# BT2.net
KiCad netlist of a schematic drawn in Altium Designer
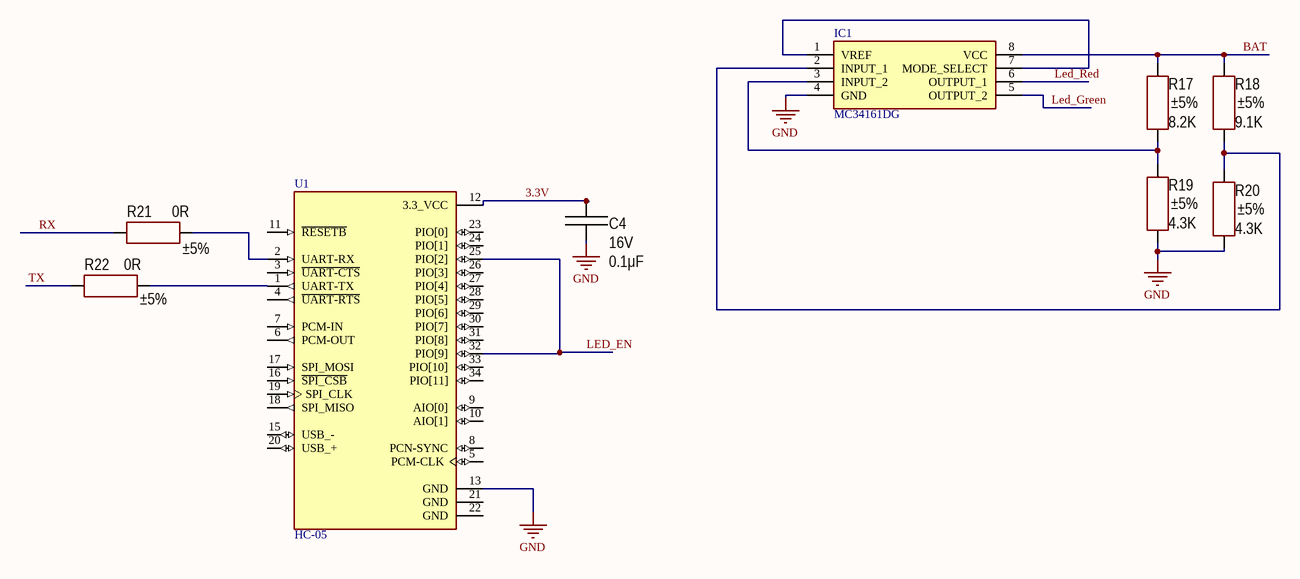
[diagram p0: BT2.SchDoc]

(export (version "E")
  (design (tool "Eeschema 10.0.6"))
  (components
    (comp (ref "C4")
      (value "0.1μF")
      (footprint "standard-case:CAP: 0805")
      (fields
        (field (name "MANUFACTURER") "Yageo")
        (field (name "PARTNUMBER") "CC0805KRX7R7BB104")
        (field (name "VALUEMANUFACTURERPARTNUMBER") "Ceramic capacitor, 0.1μF, X7R, ±10%, 16V, 0805, -55...+125°C")
        (field (name "VOLTAGE") "16V")
      )
      (libsource (lib "capacitor") (part "Ceramic_0805"))
    )
    (comp (ref "IC1")
      (value "MC34161DG")
      (footprint "SamacSys:SOIC127P600X175-8N")
      (description "Integrated Circuit")
      (fields (field (name "MOUSER PART NUMBER") "863-MC34161DG"))
      (libsource (lib "*") (part "MC34161DG"))
    )
    (comp (ref "R17")
      (value "8.2K")
      (footprint "standard-case:RES: 0805")
      (fields
        (field (name "MANUFACTURER") "Yageo")
        (field (name "PARTNUMBER") "RC0805JR-078K2L")
        (field (name "VALUEMANUFACTURERPARTNUMBER") "Resistor film, 8.2K, ±5%, 0805, 0.125W, -55...+125°C")
        (field (name "TOLERANCE") "±5%")
      )
      (libsource (lib "") (part "Resistor_0805_1"))
    )
    (comp (ref "R18")
      (value "9.1K")
      (footprint "standard-case:RES: 0805")
      (fields
        (field (name "MANUFACTURER") "Yageo")
        (field (name "PARTNUMBER") "RC0805JR-079K1L")
        (field (name "VALUEMANUFACTURERPARTNUMBER") "Resistor film, 9.1K, ±5%, 0805, 0.125W, -55...+125°C")
        (field (name "TOLERANCE") "±5%")
      )
      (libsource (lib "") (part "Resistor_0805_1"))
    )
    (comp (ref "R19")
      (value "4.3K")
      (footprint "standard-case:RES: 0805")
      (fields
        (field (name "MANUFACTURER") "Yageo")
        (field (name "PARTNUMBER") "RC0805JR-074K3L")
        (field (name "VALUEMANUFACTURERPARTNUMBER") "Resistor film, 4.3K, ±5%, 0805, 0.125W, -55...+125°C")
        (field (name "TOLERANCE") "±5%")
      )
      (libsource (lib "") (part "Resistor_0805_1"))
    )
    (comp (ref "R20")
      (value "4.3K")
      (footprint "standard-case:RES: 0805")
      (fields
        (field (name "MANUFACTURER") "Yageo")
        (field (name "PARTNUMBER") "RC0805JR-074K3L")
        (field (name "VALUEMANUFACTURERPARTNUMBER") "Resistor film, 4.3K, ±5%, 0805, 0.125W, -55...+125°C")
        (field (name "TOLERANCE") "±5%")
      )
      (libsource (lib "") (part "Resistor_0805_1"))
    )
    (comp (ref "R21")
      (value "0R")
      (footprint "standard-case:RES: 0805")
      (fields
        (field (name "MANUFACTURER") "Yageo")
        (field (name "PARTNUMBER") "RC0805JR-070RL")
        (field (name "VALUEMANUFACTURERPARTNUMBER") "Resistor film, 0R, ±5%, 0805, 0.125W, -55...+125°C")
        (field (name "TOLERANCE") "±5%")
      )
      (libsource (lib "resistor") (part "Resistor_0805"))
    )
    (comp (ref "R22")
      (value "0R")
      (footprint "standard-case:RES: 0805")
      (fields
        (field (name "MANUFACTURER") "Yageo")
        (field (name "PARTNUMBER") "RC0805JR-070RL")
        (field (name "VALUEMANUFACTURERPARTNUMBER") "Resistor film, 0R, ±5%, 0805, 0.125W, -55...+125°C")
        (field (name "TOLERANCE") "±5%")
      )
      (libsource (lib "resistor") (part "Resistor_0805"))
    )
    (comp (ref "U1")
      (value "HC-05")
      (footprint "XCVR_HC-05")
      (description "Bluetooth to Serial Port Module")
      (fields (field (name "MF") "ITead Studio"))
      (libsource (lib "HC-05 (1)") (part "HC-05"))
    )
  )
  (nets
    (net (code "1") (name "/3.3V") (class "Default")
      (node (ref "C4") (pin "2") (pinfunction "2_2") (pintype "passive"))
      (node (ref "U1") (pin "12") (pinfunction "3.3_VCC_12") (pintype "power_in"))
    )
    (net (code "2") (name "/BAT") (class "Default")
      (node (ref "IC1") (pin "8") (pinfunction "VCC_8") (pintype "passive"))
      (node (ref "R17") (pin "2") (pinfunction "2_2") (pintype "passive"))
      (node (ref "R18") (pin "2") (pinfunction "2_2") (pintype "passive"))
    )
    (net (code "3") (name "/LED_EN") (class "Default")
      (node (ref "U1") (pin "25") (pinfunction "PIO[2]_25") (pintype "bidirectional"))
      (node (ref "U1") (pin "32") (pinfunction "PIO[9]_32") (pintype "bidirectional"))
    )
    (net (code "4") (name "/Led_Green") (class "Default")
      (node (ref "IC1") (pin "5") (pinfunction "OUTPUT_2_5") (pintype "passive"))
    )
    (net (code "5") (name "/Led_Red") (class "Default")
      (node (ref "IC1") (pin "6") (pinfunction "OUTPUT_1_6") (pintype "passive"))
    )
    (net (code "6") (name "/RX") (class "Default")
      (node (ref "R21") (pin "1") (pinfunction "1_1") (pintype "passive"))
    )
    (net (code "7") (name "/TX") (class "Default")
      (node (ref "R22") (pin "1") (pinfunction "1_1") (pintype "passive"))
    )
    (net (code "8") (name "GND") (class "Default")
      (node (ref "C4") (pin "1") (pinfunction "1_1") (pintype "passive"))
      (node (ref "IC1") (pin "4") (pinfunction "GND_4") (pintype "passive"))
      (node (ref "R19") (pin "1") (pinfunction "1_1") (pintype "passive"))
      (node (ref "R20") (pin "1") (pinfunction "1_1") (pintype "passive"))
      (node (ref "U1") (pin "13") (pinfunction "GND_13") (pintype "power_in"))
    )
    (net (code "9") (name "Net-(IC1-INPUT_1)") (class "Default")
      (node (ref "IC1") (pin "2") (pinfunction "INPUT_1_2") (pintype "passive"))
      (node (ref "R18") (pin "1") (pinfunction "1_1") (pintype "passive"))
      (node (ref "R20") (pin "2") (pinfunction "2_2") (pintype "passive"))
    )
    (net (code "10") (name "Net-(IC1-INPUT_2)") (class "Default")
      (node (ref "IC1") (pin "3") (pinfunction "INPUT_2_3") (pintype "passive"))
      (node (ref "R17") (pin "1") (pinfunction "1_1") (pintype "passive"))
      (node (ref "R19") (pin "2") (pinfunction "2_2") (pintype "passive"))
    )
    (net (code "11") (name "Net-(IC1-MODE_SELECT)") (class "Default")
      (node (ref "IC1") (pin "1") (pinfunction "VREF_1") (pintype "passive"))
      (node (ref "IC1") (pin "7") (pinfunction "MODE_SELECT_7") (pintype "passive"))
    )
    (net (code "12") (name "Net-(U1-UART-RX)") (class "Default")
      (node (ref "R21") (pin "2") (pinfunction "2_2") (pintype "passive"))
      (node (ref "U1") (pin "2") (pinfunction "UART-RX_2") (pintype "input"))
    )
    (net (code "13") (name "Net-(U1-UART-TX)") (class "Default")
      (node (ref "R22") (pin "2") (pinfunction "2_2") (pintype "passive"))
      (node (ref "U1") (pin "1") (pinfunction "UART-TX_1") (pintype "output"))
    )
    (net (code "14") (name "unconnected-(U1-AIO[0]-Pad9)") (class "Default")
      (node (ref "U1") (pin "9") (pinfunction "AIO[0]_9") (pintype "bidirectional"))
    )
    (net (code "15") (name "unconnected-(U1-AIO[1]-Pad10)") (class "Default")
      (node (ref "U1") (pin "10") (pinfunction "AIO[1]_10") (pintype "bidirectional"))
    )
    (net (code "16") (name "unconnected-(U1-GND-Pad21)") (class "Default")
      (node (ref "U1") (pin "21") (pinfunction "GND_21") (pintype "power_in"))
    )
    (net (code "17") (name "unconnected-(U1-GND-Pad22)") (class "Default")
      (node (ref "U1") (pin "22") (pinfunction "GND_22") (pintype "power_in"))
    )
    (net (code "18") (name "unconnected-(U1-PCM-CLK-Pad5)") (class "Default")
      (node (ref "U1") (pin "5") (pinfunction "PCM-CLK_5") (pintype "bidirectional"))
    )
    (net (code "19") (name "unconnected-(U1-PCM-IN-Pad7)") (class "Default")
      (node (ref "U1") (pin "7") (pinfunction "PCM-IN_7") (pintype "input"))
    )
    (net (code "20") (name "unconnected-(U1-PCM-OUT-Pad6)") (class "Default")
      (node (ref "U1") (pin "6") (pinfunction "PCM-OUT_6") (pintype "output"))
    )
    (net (code "21") (name "unconnected-(U1-PCN-SYNC-Pad8)") (class "Default")
      (node (ref "U1") (pin "8") (pinfunction "PCN-SYNC_8") (pintype "bidirectional"))
    )
    (net (code "22") (name "unconnected-(U1-PIO[0]-Pad23)") (class "Default")
      (node (ref "U1") (pin "23") (pinfunction "PIO[0]_23") (pintype "bidirectional"))
    )
    (net (code "23") (name "unconnected-(U1-PIO[1]-Pad24)") (class "Default")
      (node (ref "U1") (pin "24") (pinfunction "PIO[1]_24") (pintype "bidirectional"))
    )
    (net (code "24") (name "unconnected-(U1-PIO[3]-Pad26)") (class "Default")
      (node (ref "U1") (pin "26") (pinfunction "PIO[3]_26") (pintype "bidirectional"))
    )
    (net (code "25") (name "unconnected-(U1-PIO[4]-Pad27)") (class "Default")
      (node (ref "U1") (pin "27") (pinfunction "PIO[4]_27") (pintype "bidirectional"))
    )
    (net (code "26") (name "unconnected-(U1-PIO[5]-Pad28)") (class "Default")
      (node (ref "U1") (pin "28") (pinfunction "PIO[5]_28") (pintype "bidirectional"))
    )
    (net (code "27") (name "unconnected-(U1-PIO[6]-Pad29)") (class "Default")
      (node (ref "U1") (pin "29") (pinfunction "PIO[6]_29") (pintype "bidirectional"))
    )
    (net (code "28") (name "unconnected-(U1-PIO[7]-Pad30)") (class "Default")
      (node (ref "U1") (pin "30") (pinfunction "PIO[7]_30") (pintype "bidirectional"))
    )
    (net (code "29") (name "unconnected-(U1-PIO[8]-Pad31)") (class "Default")
      (node (ref "U1") (pin "31") (pinfunction "PIO[8]_31") (pintype "bidirectional"))
    )
    (net (code "30") (name "unconnected-(U1-PIO[10]-Pad33)") (class "Default")
      (node (ref "U1") (pin "33") (pinfunction "PIO[10]_33") (pintype "bidirectional"))
    )
    (net (code "31") (name "unconnected-(U1-PIO[11]-Pad34)") (class "Default")
      (node (ref "U1") (pin "34") (pinfunction "PIO[11]_34") (pintype "bidirectional"))
    )
    (net (code "32") (name "unconnected-(U1-SPI_CLK-Pad19)") (class "Default")
      (node (ref "U1") (pin "19") (pinfunction "SPI_CLK_19") (pintype "input"))
    )
    (net (code "33") (name "unconnected-(U1-SPI_MISO-Pad18)") (class "Default")
      (node (ref "U1") (pin "18") (pinfunction "SPI_MISO_18") (pintype "output"))
    )
    (net (code "34") (name "unconnected-(U1-SPI_MOSI-Pad17)") (class "Default")
      (node (ref "U1") (pin "17") (pinfunction "SPI_MOSI_17") (pintype "input"))
    )
    (net (code "35") (name "unconnected-(U1-USB_+-Pad20)") (class "Default")
      (node (ref "U1") (pin "20") (pinfunction "USB_+_20") (pintype "bidirectional"))
    )
    (net (code "36") (name "unconnected-(U1-USB_--Pad15)") (class "Default")
      (node (ref "U1") (pin "15") (pinfunction "USB_-_15") (pintype "bidirectional"))
    )
    (net (code "37") (name "unconnected-(U1-~{RESETB}-Pad11)") (class "Default")
      (node (ref "U1") (pin "11") (pinfunction "~{RESETB}_11") (pintype "input"))
    )
    (net (code "38") (name "unconnected-(U1-~{SPI_CSB}-Pad16)") (class "Default")
      (node (ref "U1") (pin "16") (pinfunction "~{SPI_CSB}_16") (pintype "input"))
    )
    (net (code "39") (name "unconnected-(U1-~{UART-CTS}-Pad3)") (class "Default")
      (node (ref "U1") (pin "3") (pinfunction "~{UART-CTS}_3") (pintype "input"))
    )
    (net (code "40") (name "unconnected-(U1-~{UART-RTS}-Pad4)") (class "Default")
      (node (ref "U1") (pin "4") (pinfunction "~{UART-RTS}_4") (pintype "output"))
    )
  )
)
